# 8_Conectors.net
KiCad netlist of a schematic drawn in Altium Designer
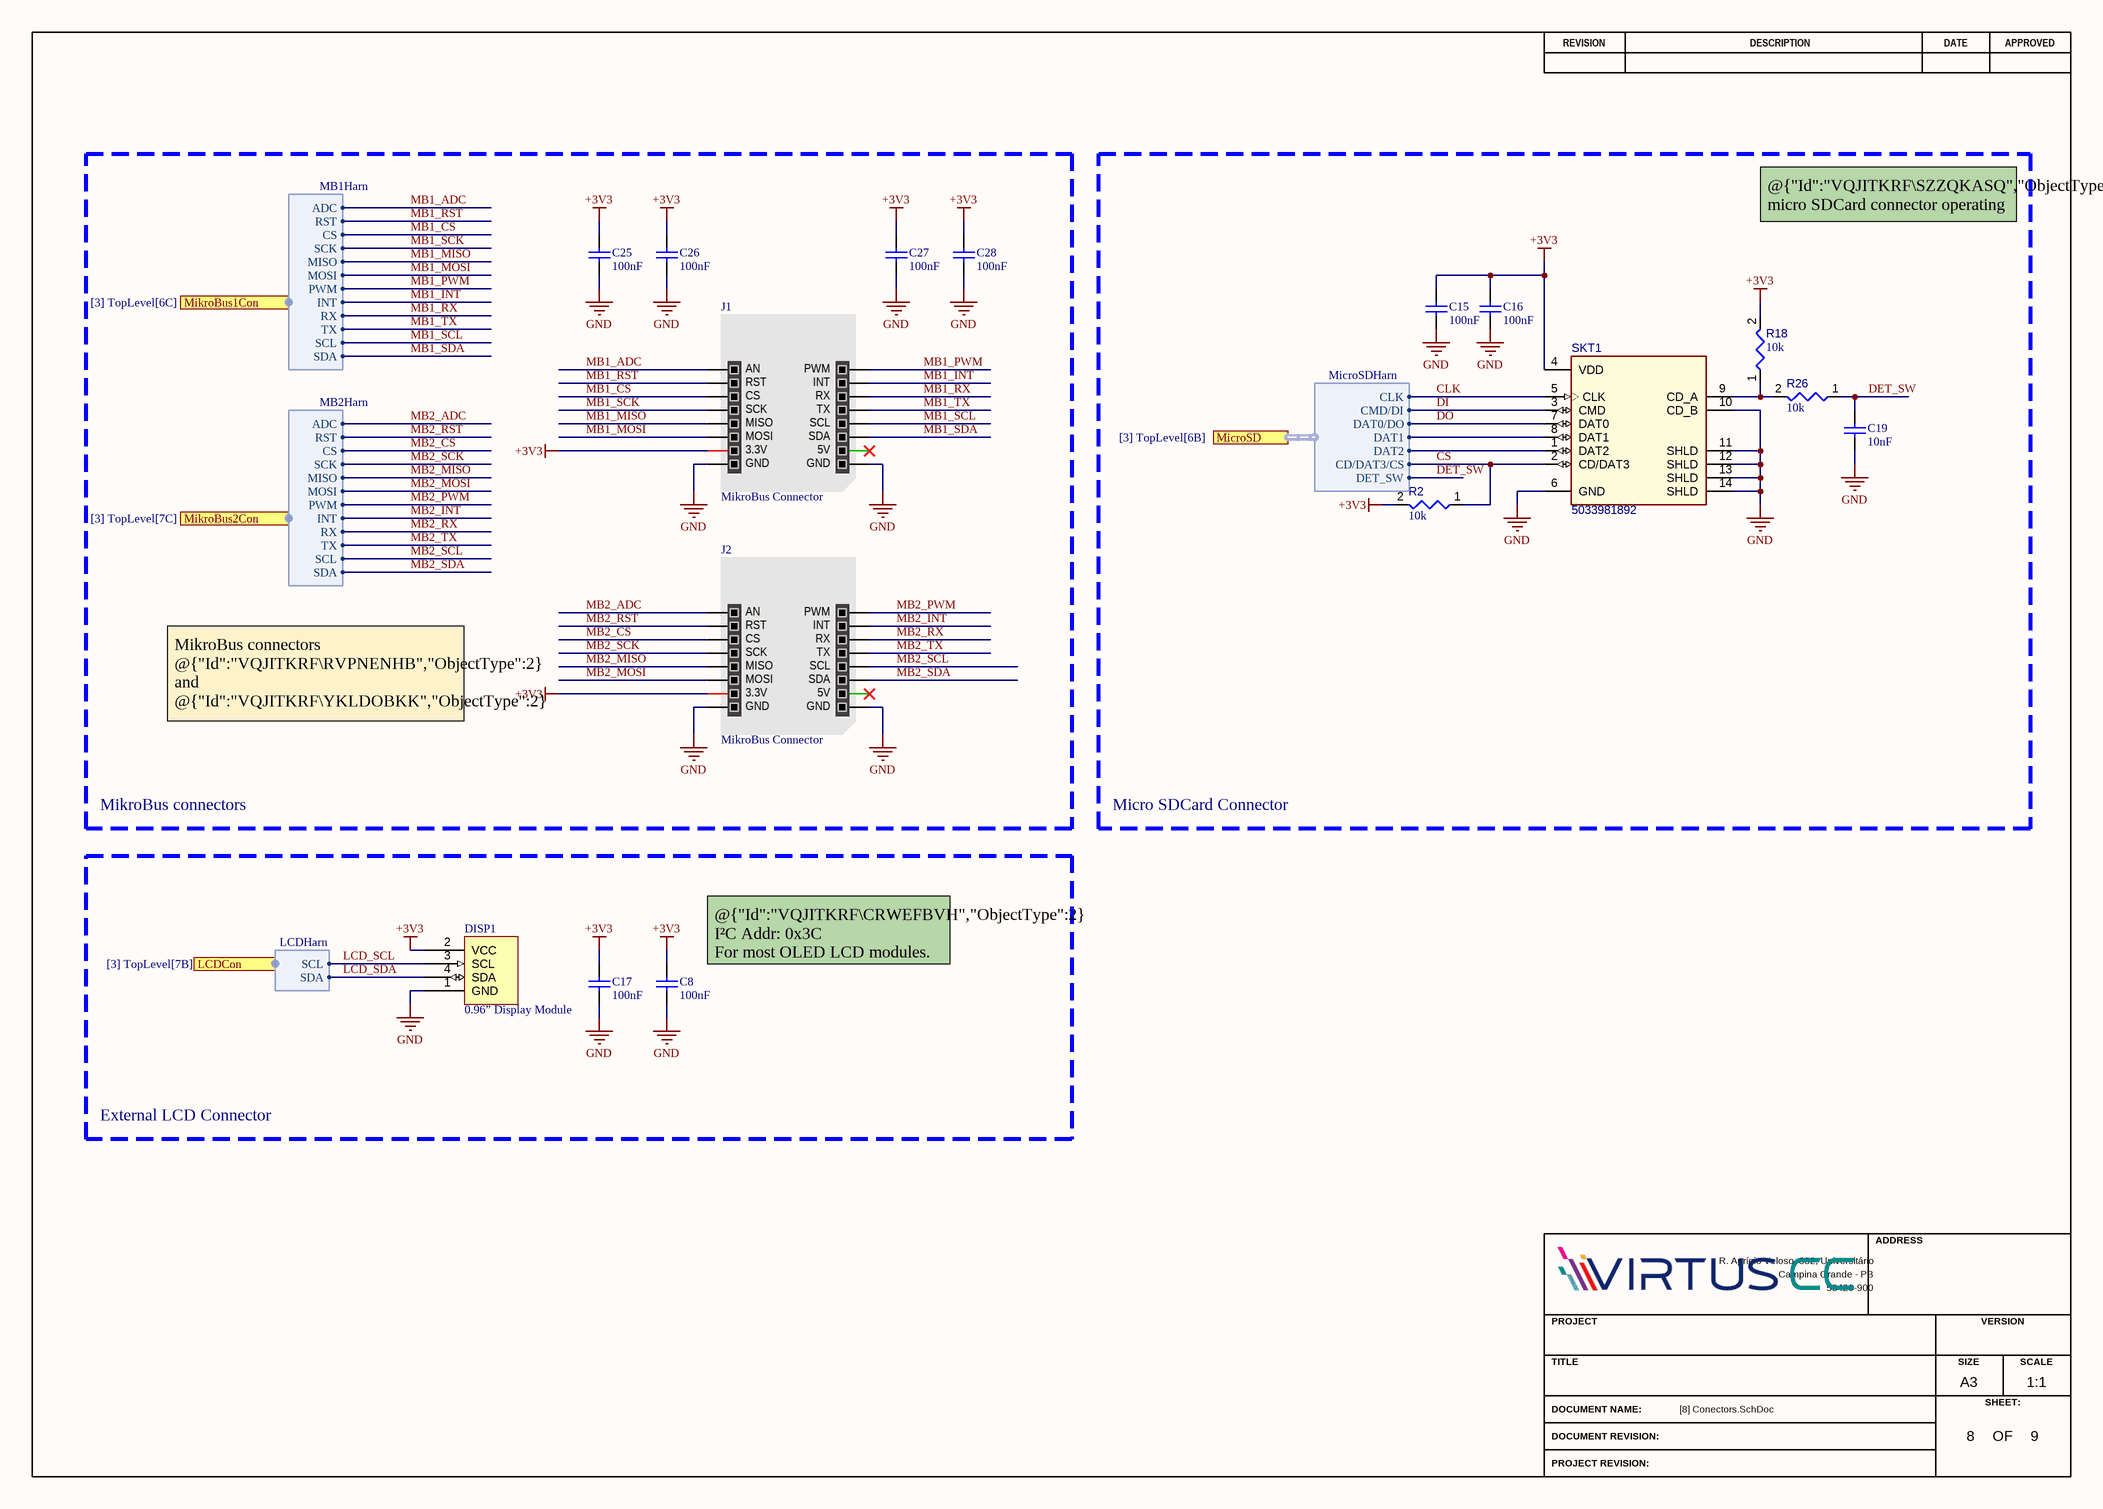
[diagram p0: [8] Conectors.SchDoc]

(export (version "E")
  (design (tool "Eeschema 10.0.6"))
  (components
    (comp (ref "C8")
      (value "100nF")
      (footprint "CAPC0603(1608)100_L")
      (description "Multilayer Ceramic Capacitor, 0.1 uF, 16 V, ± 20%, X7R, 0603 [1608 Metric]")
      (fields (field (name "TOLERANCE") "20%") (field (name "Comment") "VJ0603Y104MXJCW1BC"))
      (libsource (lib "UFCG - Universidade Federal de Campina Grande") (part "CAP"))
    )
    (comp (ref "C15")
      (value "100nF")
      (footprint "CAPC0603(1608)100_L")
      (description "Multilayer Ceramic Capacitor, 0.1 uF, 16 V, ± 20%, X7R, 0603 [1608 Metric]")
      (fields (field (name "TOLERANCE") "20%") (field (name "Comment") "VJ0603Y104MXJCW1BC"))
      (libsource (lib "UFCG - Universidade Federal de Campina Grande") (part "CAP"))
    )
    (comp (ref "C16")
      (value "100nF")
      (footprint "CAPC0603(1608)100_L")
      (description "Multilayer Ceramic Capacitor, 0.1 uF, 16 V, ± 20%, X7R, 0603 [1608 Metric]")
      (fields (field (name "TOLERANCE") "20%") (field (name "Comment") "VJ0603Y104MXJCW1BC"))
      (libsource (lib "UFCG - Universidade Federal de Campina Grande") (part "CAP"))
    )
    (comp (ref "C17")
      (value "100nF")
      (footprint "CAPC0603(1608)100_L")
      (description "Multilayer Ceramic Capacitor, 0.1 uF, 16 V, ± 20%, X7R, 0603 [1608 Metric]")
      (fields (field (name "TOLERANCE") "20%") (field (name "Comment") "VJ0603Y104MXJCW1BC"))
      (libsource (lib "UFCG - Universidade Federal de Campina Grande") (part "CAP"))
    )
    (comp (ref "C19")
      (value "10nF")
      (footprint "CAPC0603(1608)100_L")
      (description "Multilayer Ceramic Capacitor, 0.01 uF, 50 V, ± 10%, X7R, 0603 [1608 Metric]")
      (fields (field (name "VOLTAGE") "50V") (field (name "TOLERANCE") "10%"))
      (libsource (lib "UFCG - Universidade Federal de Campina Grande") (part "CAP"))
    )
    (comp (ref "C25")
      (value "100nF")
      (footprint "CAPC0603(1608)100_L")
      (description "Multilayer Ceramic Capacitor, 0.1 uF, 16 V, ± 20%, X7R, 0603 [1608 Metric]")
      (fields (field (name "TOLERANCE") "20%") (field (name "Comment") "VJ0603Y104MXJCW1BC"))
      (libsource (lib "UFCG - Universidade Federal de Campina Grande") (part "CAP"))
    )
    (comp (ref "C26")
      (value "100nF")
      (footprint "CAPC0603(1608)100_L")
      (description "Multilayer Ceramic Capacitor, 0.1 uF, 16 V, ± 20%, X7R, 0603 [1608 Metric]")
      (fields (field (name "TOLERANCE") "20%") (field (name "Comment") "VJ0603Y104MXJCW1BC"))
      (libsource (lib "UFCG - Universidade Federal de Campina Grande") (part "CAP"))
    )
    (comp (ref "C27")
      (value "100nF")
      (footprint "CAPC0603(1608)100_L")
      (description "Multilayer Ceramic Capacitor, 0.1 uF, 16 V, ± 20%, X7R, 0603 [1608 Metric]")
      (fields (field (name "TOLERANCE") "20%") (field (name "Comment") "VJ0603Y104MXJCW1BC"))
      (libsource (lib "UFCG - Universidade Federal de Campina Grande") (part "CAP"))
    )
    (comp (ref "C28")
      (value "100nF")
      (footprint "CAPC0603(1608)100_L")
      (description "Multilayer Ceramic Capacitor, 0.1 uF, 16 V, ± 20%, X7R, 0603 [1608 Metric]")
      (fields (field (name "TOLERANCE") "20%") (field (name "Comment") "VJ0603Y104MXJCW1BC"))
      (libsource (lib "UFCG - Universidade Federal de Campina Grande") (part "CAP"))
    )
    (comp (ref "DISP1")
      (value "0.96” Display Module")
      (footprint "New footprint 1")
      (description "0.96 Inch I2C OLED Display Module")
      (libsource (lib "UFCG - Universidade Federal de Campina Grande") (part "0.96{dblquote} Display"))
    )
    (comp (ref "J1")
      (value "MikroBus Connector")
      (footprint "New footprint 1")
      (description "MikroBus shield pico")
      (libsource (lib "UFCG - Universidade Federal de Campina Grande") (part "MikroBus connector"))
    )
    (comp (ref "J2")
      (value "MikroBus Connector")
      (footprint "New footprint 1")
      (description "MikroBus shield pico")
      (libsource (lib "UFCG - Universidade Federal de Campina Grande") (part "MikroBus connector"))
    )
    (comp (ref "R2")
      (value "10k")
      (footprint "RESC0603(1608)_L")
      (description "Chip Resistor, 10 KOhm, +/- 1%, 01 W, -55 to 155 degC, 0603 (1608 Metric)")
      (fields (field (name "POWER") "100mW") (field (name "TOLERANCE") "1%"))
      (libsource (lib "UFCG - Universidade Federal de Campina Grande") (part "RES-2"))
    )
    (comp (ref "R18")
      (value "10k")
      (footprint "RESC0603(1608)_L")
      (description "Chip Resistor, 10 KOhm, +/- 1%, 01 W, -55 to 155 degC, 0603 (1608 Metric)")
      (fields (field (name "POWER") "100mW") (field (name "TOLERANCE") "1%"))
      (libsource (lib "UFCG - Universidade Federal de Campina Grande") (part "RES-2"))
    )
    (comp (ref "R26")
      (value "10k")
      (footprint "RESC0603(1608)_L")
      (description "Chip Resistor, 10 KOhm, +/- 1%, 01 W, -55 to 155 degC, 0603 (1608 Metric)")
      (fields (field (name "POWER") "100mW") (field (name "TOLERANCE") "1%"))
      (libsource (lib "UFCG - Universidade Federal de Campina Grande") (part "RES-2"))
    )
    (comp (ref "SKT1")
      (value "5033981892")
      (footprint "MOLX-5033981892_V")
      (libsource (lib "UFCG - Universidade Federal de Campina Grande") (part "CMP-00040-6"))
    )
  )
  (nets
    (net (code "5") (name "+3V3") (class "Default")
      (node (ref "C15") (pin "2") (pinfunction "2_2") (pintype "passive"))
      (node (ref "C16") (pin "2") (pinfunction "2_2") (pintype "passive"))
      (node (ref "C17") (pin "2") (pinfunction "2_2") (pintype "passive"))
      (node (ref "C25") (pin "2") (pinfunction "2_2") (pintype "passive"))
      (node (ref "C26") (pin "2") (pinfunction "2_2") (pintype "passive"))
      (node (ref "C27") (pin "2") (pinfunction "2_2") (pintype "passive"))
      (node (ref "C28") (pin "2") (pinfunction "2_2") (pintype "passive"))
      (node (ref "C8") (pin "2") (pinfunction "2_2") (pintype "passive"))
      (node (ref "DISP1") (pin "2") (pinfunction "VCC_2") (pintype "power_in"))
      (node (ref "J1") (pin "7") (pinfunction "3.3V_7") (pintype "passive"))
      (node (ref "J2") (pin "7") (pinfunction "3.3V_7") (pintype "passive"))
      (node (ref "R18") (pin "2") (pinfunction "2_2") (pintype "passive"))
      (node (ref "R2") (pin "2") (pinfunction "2_2") (pintype "passive"))
      (node (ref "SKT1") (pin "4") (pinfunction "VDD_4") (pintype "power_in"))
    )
    (net (code "6") (name "/CLK") (class "Default")
      (node (ref "SKT1") (pin "5") (pinfunction "CLK_5") (pintype "input"))
    )
    (net (code "7") (name "/CS") (class "Default")
      (node (ref "R2") (pin "1") (pinfunction "1_1") (pintype "passive"))
      (node (ref "SKT1") (pin "2") (pinfunction "CD/DAT3_2") (pintype "bidirectional"))
    )
    (net (code "8") (name "/DAT1") (class "Default")
      (node (ref "SKT1") (pin "8") (pinfunction "DAT1_8") (pintype "bidirectional"))
    )
    (net (code "9") (name "/DAT2") (class "Default")
      (node (ref "SKT1") (pin "1") (pinfunction "DAT2_1") (pintype "bidirectional"))
    )
    (net (code "10") (name "/DET_SW") (class "Default")
      (node (ref "C19") (pin "2") (pinfunction "2_2") (pintype "passive"))
      (node (ref "R26") (pin "1") (pinfunction "1_1") (pintype "passive"))
    )
    (net (code "11") (name "/DI") (class "Default")
      (node (ref "SKT1") (pin "3") (pinfunction "CMD_3") (pintype "bidirectional"))
    )
    (net (code "12") (name "/DO") (class "Default")
      (node (ref "SKT1") (pin "7") (pinfunction "DAT0_7") (pintype "bidirectional"))
    )
    (net (code "13") (name "/LCD_SCL") (class "Default")
      (node (ref "DISP1") (pin "3") (pinfunction "SCL_3") (pintype "input"))
    )
    (net (code "14") (name "/LCD_SDA") (class "Default")
      (node (ref "DISP1") (pin "4") (pinfunction "SDA_4") (pintype "bidirectional"))
    )
    (net (code "15") (name "/MB1_ADC") (class "Default")
      (node (ref "J1") (pin "1") (pinfunction "AN_1") (pintype "passive"))
    )
    (net (code "16") (name "/MB1_CS") (class "Default")
      (node (ref "J1") (pin "3") (pinfunction "CS_3") (pintype "passive"))
    )
    (net (code "17") (name "/MB1_INT") (class "Default")
      (node (ref "J1") (pin "15") (pinfunction "INT_15") (pintype "passive"))
    )
    (net (code "18") (name "/MB1_MISO") (class "Default")
      (node (ref "J1") (pin "5") (pinfunction "MISO_5") (pintype "passive"))
    )
    (net (code "19") (name "/MB1_MOSI") (class "Default")
      (node (ref "J1") (pin "6") (pinfunction "MOSI_6") (pintype "passive"))
    )
    (net (code "20") (name "/MB1_PWM") (class "Default")
      (node (ref "J1") (pin "16") (pinfunction "PWM_16") (pintype "passive"))
    )
    (net (code "21") (name "/MB1_RST") (class "Default")
      (node (ref "J1") (pin "2") (pinfunction "RST_2") (pintype "passive"))
    )
    (net (code "22") (name "/MB1_RX") (class "Default")
      (node (ref "J1") (pin "14") (pinfunction "RX_14") (pintype "passive"))
    )
    (net (code "23") (name "/MB1_SCK") (class "Default")
      (node (ref "J1") (pin "4") (pinfunction "SCK_4") (pintype "passive"))
    )
    (net (code "24") (name "/MB1_SCL") (class "Default")
      (node (ref "J1") (pin "12") (pinfunction "SCL_12") (pintype "passive"))
    )
    (net (code "25") (name "/MB1_SDA") (class "Default")
      (node (ref "J1") (pin "11") (pinfunction "SDA_11") (pintype "passive"))
    )
    (net (code "26") (name "/MB1_TX") (class "Default")
      (node (ref "J1") (pin "13") (pinfunction "TX_13") (pintype "passive"))
    )
    (net (code "27") (name "/MB2_ADC") (class "Default")
      (node (ref "J2") (pin "1") (pinfunction "AN_1") (pintype "passive"))
    )
    (net (code "28") (name "/MB2_CS") (class "Default")
      (node (ref "J2") (pin "3") (pinfunction "CS_3") (pintype "passive"))
    )
    (net (code "29") (name "/MB2_INT") (class "Default")
      (node (ref "J2") (pin "15") (pinfunction "INT_15") (pintype "passive"))
    )
    (net (code "30") (name "/MB2_MISO") (class "Default")
      (node (ref "J2") (pin "5") (pinfunction "MISO_5") (pintype "passive"))
    )
    (net (code "31") (name "/MB2_MOSI") (class "Default")
      (node (ref "J2") (pin "6") (pinfunction "MOSI_6") (pintype "passive"))
    )
    (net (code "32") (name "/MB2_PWM") (class "Default")
      (node (ref "J2") (pin "16") (pinfunction "PWM_16") (pintype "passive"))
    )
    (net (code "33") (name "/MB2_RST") (class "Default")
      (node (ref "J2") (pin "2") (pinfunction "RST_2") (pintype "passive"))
    )
    (net (code "34") (name "/MB2_RX") (class "Default")
      (node (ref "J2") (pin "14") (pinfunction "RX_14") (pintype "passive"))
    )
    (net (code "35") (name "/MB2_SCK") (class "Default")
      (node (ref "J2") (pin "4") (pinfunction "SCK_4") (pintype "passive"))
    )
    (net (code "36") (name "/MB2_SCL") (class "Default")
      (node (ref "J2") (pin "12") (pinfunction "SCL_12") (pintype "passive"))
    )
    (net (code "37") (name "/MB2_SDA") (class "Default")
      (node (ref "J2") (pin "11") (pinfunction "SDA_11") (pintype "passive"))
    )
    (net (code "38") (name "/MB2_TX") (class "Default")
      (node (ref "J2") (pin "13") (pinfunction "TX_13") (pintype "passive"))
    )
    (net (code "43") (name "GND") (class "Default")
      (node (ref "C15") (pin "1") (pinfunction "1_1") (pintype "passive"))
      (node (ref "C16") (pin "1") (pinfunction "1_1") (pintype "passive"))
      (node (ref "C17") (pin "1") (pinfunction "1_1") (pintype "passive"))
      (node (ref "C19") (pin "1") (pinfunction "1_1") (pintype "passive"))
      (node (ref "C25") (pin "1") (pinfunction "1_1") (pintype "passive"))
      (node (ref "C26") (pin "1") (pinfunction "1_1") (pintype "passive"))
      (node (ref "C27") (pin "1") (pinfunction "1_1") (pintype "passive"))
      (node (ref "C28") (pin "1") (pinfunction "1_1") (pintype "passive"))
      (node (ref "C8") (pin "1") (pinfunction "1_1") (pintype "passive"))
      (node (ref "DISP1") (pin "1") (pinfunction "GND_1") (pintype "power_in"))
      (node (ref "J1") (pin "8") (pinfunction "GND_8") (pintype "passive"))
      (node (ref "J1") (pin "9") (pinfunction "GND_9") (pintype "passive"))
      (node (ref "J2") (pin "8") (pinfunction "GND_8") (pintype "passive"))
      (node (ref "J2") (pin "9") (pinfunction "GND_9") (pintype "passive"))
      (node (ref "SKT1") (pin "10") (pinfunction "CD_B_10") (pintype "passive"))
      (node (ref "SKT1") (pin "11") (pinfunction "SHLD_11") (pintype "passive"))
      (node (ref "SKT1") (pin "12") (pinfunction "SHLD_12") (pintype "passive"))
      (node (ref "SKT1") (pin "13") (pinfunction "SHLD_13") (pintype "passive"))
      (node (ref "SKT1") (pin "14") (pinfunction "SHLD_14") (pintype "passive"))
      (node (ref "SKT1") (pin "6") (pinfunction "GND_6") (pintype "passive"))
    )
    (net (code "44") (name "Net-(SKT1-CD_A)") (class "Default")
      (node (ref "R18") (pin "1") (pinfunction "1_1") (pintype "passive"))
      (node (ref "R26") (pin "2") (pinfunction "2_2") (pintype "passive"))
      (node (ref "SKT1") (pin "9") (pinfunction "CD_A_9") (pintype "passive"))
    )
    (net (code "45") (name "unconnected-(J1-5V-Pad10)") (class "Default")
      (node (ref "J1") (pin "10") (pinfunction "5V_10") (pintype "passive+no_connect"))
    )
    (net (code "46") (name "unconnected-(J2-5V-Pad10)") (class "Default")
      (node (ref "J2") (pin "10") (pinfunction "5V_10") (pintype "passive+no_connect"))
    )
  )
)
